# micro_flight.net
KiCad netlist of a schematic drawn in Altium Designer
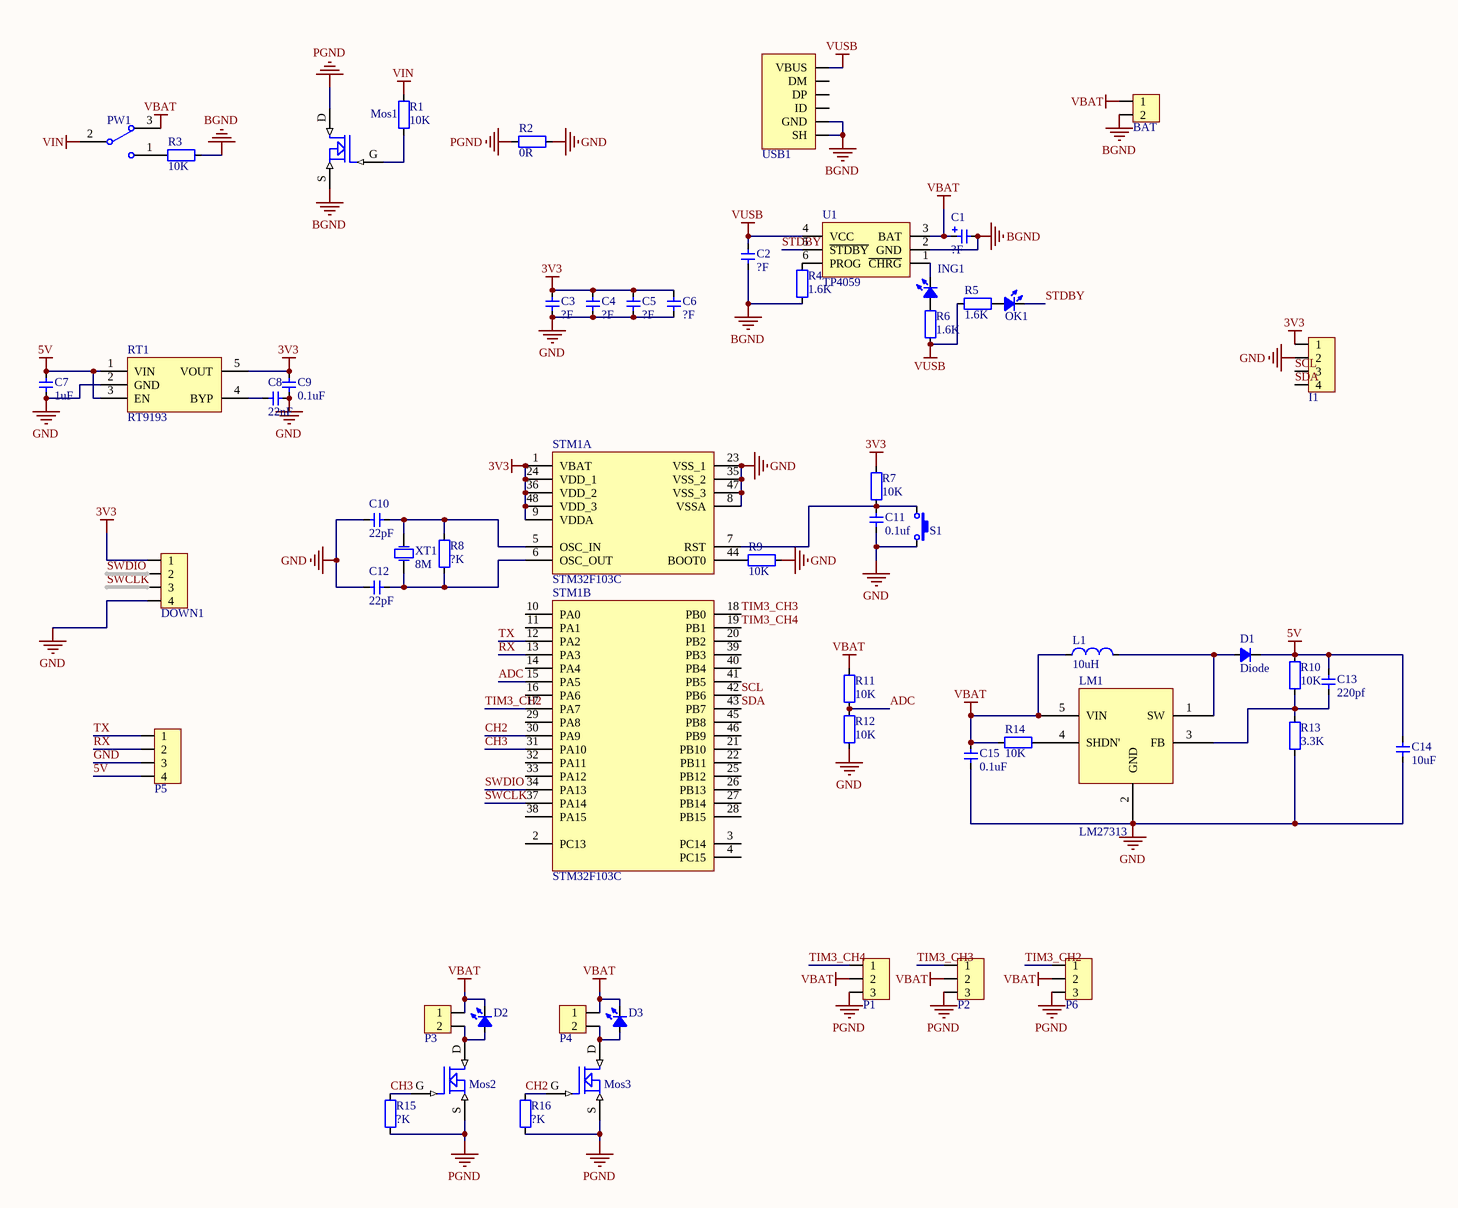
[diagram p0: micro_flight.SchDoc]

(export (version "E")
  (design (tool "Eeschema 10.0.6"))
  (components
    (comp (ref "BAT")
      (value "HDR1x2_2.54")
      (footprint "PCB_ConnectorHDR:HDR1X2_2.54_90")
      (description "Header")
      (libsource (lib "SCH_ConnectorHDR") (part "HDR1x2_2.54"))
    )
    (comp (ref "C1")
      (value "?F")
      (footprint "PCB_PassiveCap:CAP_TAN_D2917")
      (description "Capacitor")
      (fields (field (name "Comment") "Cap_Tan_2917"))
      (libsource (lib "SCH_Passive") (part "Cap_Tan_2917"))
    )
    (comp (ref "C2")
      (value "?F")
      (footprint "PCB_PassiveCap:CAP_0805")
      (description "Capacitor")
      (fields (field (name "Comment") "Cap_0805"))
      (libsource (lib "SCH_Passive") (part "Cap_0805"))
    )
    (comp (ref "C3")
      (value "?F")
      (footprint "PCB_PassiveCap:CAP_0805")
      (description "Capacitor")
      (fields (field (name "Comment") "Cap_0805"))
      (libsource (lib "SCH_Passive") (part "Cap_0805"))
    )
    (comp (ref "C4")
      (value "?F")
      (footprint "PCB_PassiveCap:CAP_0805")
      (description "Capacitor")
      (fields (field (name "Comment") "Cap_0805"))
      (libsource (lib "SCH_Passive") (part "Cap_0805"))
    )
    (comp (ref "C5")
      (value "?F")
      (footprint "PCB_PassiveCap:CAP_0805")
      (description "Capacitor")
      (fields (field (name "Comment") "Cap_0805"))
      (libsource (lib "SCH_Passive") (part "Cap_0805"))
    )
    (comp (ref "C6")
      (value "?F")
      (footprint "PCB_PassiveCap:CAP_0805")
      (description "Capacitor")
      (fields (field (name "Comment") "Cap_0805"))
      (libsource (lib "SCH_Passive") (part "Cap_0805"))
    )
    (comp (ref "C7")
      (value "1uF")
      (footprint "PCB_PassiveCap:CAP_0805")
      (description "Capacitor")
      (fields (field (name "Comment") "Cap_0805"))
      (libsource (lib "SCH_Passive") (part "Cap_0805"))
    )
    (comp (ref "C8")
      (value "22nF")
      (footprint "PCB_PassiveCap:CAP_0805")
      (description "Capacitor")
      (fields (field (name "Comment") "Cap_0805"))
      (libsource (lib "SCH_Passive") (part "Cap_0805"))
    )
    (comp (ref "C9")
      (value "0.1uF")
      (footprint "PCB_PassiveCap:CAP_0805")
      (description "Capacitor")
      (fields (field (name "Comment") "Cap_0805"))
      (libsource (lib "SCH_Passive") (part "Cap_0805"))
    )
    (comp (ref "C10")
      (value "22pF")
      (footprint "PCB_PassiveCap:CAP_0805")
      (description "Capacitor")
      (fields (field (name "Comment") "Cap_0805"))
      (libsource (lib "SCH_Passive") (part "Cap_0805"))
    )
    (comp (ref "C11")
      (value "0.1uf")
      (footprint "PCB_PassiveCap:CAP_0805")
      (description "Capacitor")
      (fields (field (name "Comment") "Cap_0805"))
      (libsource (lib "SCH_Passive") (part "Cap_0805"))
    )
    (comp (ref "C12")
      (value "22pF")
      (footprint "PCB_PassiveCap:CAP_0805")
      (description "Capacitor")
      (fields (field (name "Comment") "Cap_0805"))
      (libsource (lib "SCH_Passive") (part "Cap_0805"))
    )
    (comp (ref "C13")
      (value "220pf")
      (footprint "PCB_PassiveCap:CAP_0805")
      (description "Capacitor")
      (fields (field (name "Comment") "Cap_0805"))
      (libsource (lib "SCH_Passive") (part "Cap_0805"))
    )
    (comp (ref "C14")
      (value "10uF")
      (footprint "PCB_PassiveCap:CAP_0805")
      (description "Capacitor")
      (fields (field (name "Comment") "Cap_0805"))
      (libsource (lib "SCH_Passive") (part "Cap_0805"))
    )
    (comp (ref "C15")
      (value "0.1uF")
      (footprint "PCB_PassiveCap:CAP_0805")
      (description "Capacitor")
      (fields (field (name "Comment") "Cap_0805"))
      (libsource (lib "SCH_Passive") (part "Cap_0805"))
    )
    (comp (ref "D1") (value "Diode") (footprint "LED_0805_RED") (libsource (lib "SCH_Active") (part "Diode")))
    (comp (ref "D2")
      (value "LED_0805")
      (footprint "PCB_ActiveLED:LED_0805_RED")
      (description "LED")
      (libsource (lib "SCH_Active") (part "LED_0805"))
    )
    (comp (ref "D3")
      (value "LED_0805")
      (footprint "PCB_ActiveLED:LED_0805_RED")
      (description "LED")
      (libsource (lib "SCH_Active") (part "LED_0805"))
    )
    (comp (ref "DOWN1")
      (value "HDR1x4_2.54")
      (footprint "PCB_ConnectorHDR:HDR1x4_2.54_180")
      (description "Header")
      (libsource (lib "SCH_ConnectorHDR") (part "HDR1x4_2.54"))
    )
    (comp (ref "I1")
      (value "HDR1x4_2.54")
      (footprint "PCB_ConnectorHDR:HDR1x4_2.54_180")
      (description "Header")
      (libsource (lib "SCH_ConnectorHDR") (part "HDR1x4_2.54"))
    )
    (comp (ref "ING1")
      (value "LED_0805")
      (footprint "PCB_ActiveLED:LED_0805_RED")
      (description "LED")
      (libsource (lib "SCH_Active") (part "LED_0805"))
    )
    (comp (ref "L1")
      (value "10uH")
      (footprint "PCB_PassiveInd:IND_CD32")
      (description "Inductor")
      (fields (field (name "Comment") "Ind_CD32"))
      (libsource (lib "SCH_Passive") (part "Ind_CD32"))
    )
    (comp (ref "LM1")
      (value "LM27313")
      (footprint "SOT23-5")
      (libsource (lib "SCH_IntegratedCircuit") (part "LM27313"))
    )
    (comp (ref "Mos1")
      (value "MOSFET N")
      (footprint "Nmos_SOT23")
      (description "MOS SOT23")
      (libsource (lib "SCH_Active") (part "MOSFET N"))
    )
    (comp (ref "Mos2")
      (value "MOSFET N")
      (footprint "Nmos_SOT23")
      (description "MOS SOT23")
      (libsource (lib "SCH_Active") (part "MOSFET N"))
    )
    (comp (ref "Mos3")
      (value "MOSFET N")
      (footprint "Nmos_SOT23")
      (description "MOS SOT23")
      (libsource (lib "SCH_Active") (part "MOSFET N"))
    )
    (comp (ref "OK1")
      (value "LED_0805")
      (footprint "PCB_ActiveLED:LED_0805_GREEN")
      (description "LED")
      (libsource (lib "SCH_Active") (part "LED_0805"))
    )
    (comp (ref "P1")
      (value "HDR1x3_2.54")
      (footprint "PCB_ConnectorHDR:HDR1X3_2.54_180")
      (description "Header")
      (libsource (lib "SCH_ConnectorHDR") (part "HDR1x3_2.54"))
    )
    (comp (ref "P2")
      (value "HDR1x3_2.54")
      (footprint "PCB_ConnectorHDR:HDR1X3_2.54_180")
      (description "Header")
      (libsource (lib "SCH_ConnectorHDR") (part "HDR1x3_2.54"))
    )
    (comp (ref "P3")
      (value "HDR1x2_2.54")
      (footprint "PCB_ConnectorHDR:HDR1X2_2.54_180")
      (description "Header")
      (libsource (lib "SCH_ConnectorHDR") (part "HDR1x2_2.54T"))
    )
    (comp (ref "P4")
      (value "HDR1x2_2.54")
      (footprint "PCB_ConnectorHDR:HDR1X2_2.54_180")
      (description "Header")
      (libsource (lib "SCH_ConnectorHDR") (part "HDR1x2_2.54T"))
    )
    (comp (ref "P5")
      (value "HDR1x4_2.54")
      (footprint "PCB_ConnectorHDR:HDR1x4_2.54_180")
      (description "Header")
      (libsource (lib "SCH_ConnectorHDR") (part "HDR1x4_2.54"))
    )
    (comp (ref "P6")
      (value "HDR1x3_2.54")
      (footprint "PCB_ConnectorHDR:HDR1X3_2.54_180")
      (description "Header")
      (libsource (lib "SCH_ConnectorHDR") (part "HDR1x3_2.54"))
    )
    (comp (ref "PW1")
      (value "SwitchSPDT_2.8x6.6_90")
      (footprint "PCB_Switch:SwitchSPDT_2.8X6.6_90")
      (description "Switch")
      (libsource (lib "SCH_Switch") (part "SwitchSPDT_2.8x6.6_90"))
    )
    (comp (ref "R1")
      (value "10K")
      (footprint "PCB_PassiveRes:RES_0805")
      (description "Resistor")
      (fields (field (name "Comment") "Res_0805"))
      (libsource (lib "SCH_Passive") (part "Res_0805"))
    )
    (comp (ref "R2")
      (value "0R")
      (footprint "PCB_PassiveRes:RES_0805")
      (description "Resistor")
      (fields (field (name "Comment") "Res_0805"))
      (libsource (lib "") (part "Res_0805_2"))
    )
    (comp (ref "R3")
      (value "10K")
      (footprint "PCB_PassiveRes:RES_0805")
      (description "Resistor")
      (fields (field (name "Comment") "Res_0805"))
      (libsource (lib "") (part "Res_0805_2"))
    )
    (comp (ref "R4")
      (value "1.6K")
      (footprint "PCB_PassiveRes:RES_0805")
      (description "Resistor")
      (fields (field (name "Comment") "Res_0805"))
      (libsource (lib "SCH_Passive") (part "Res_0805"))
    )
    (comp (ref "R5")
      (value "1.6K")
      (footprint "PCB_PassiveRes:RES_0805")
      (description "Resistor")
      (fields (field (name "Comment") "Res_0805"))
      (libsource (lib "") (part "Res_0805_2"))
    )
    (comp (ref "R6")
      (value "1.6K")
      (footprint "PCB_PassiveRes:RES_0805")
      (description "Resistor")
      (fields (field (name "Comment") "Res_0805"))
      (libsource (lib "SCH_Passive") (part "Res_0805"))
    )
    (comp (ref "R7")
      (value "10K")
      (footprint "PCB_PassiveRes:RES_0805")
      (description "Resistor")
      (fields (field (name "Comment") "Res_0805"))
      (libsource (lib "SCH_Passive") (part "Res_0805"))
    )
    (comp (ref "R8")
      (value "?K")
      (footprint "PCB_PassiveRes:RES_0805")
      (description "Resistor")
      (fields (field (name "Comment") "Res_0805"))
      (libsource (lib "SCH_Passive") (part "Res_0805"))
    )
    (comp (ref "R9")
      (value "10K")
      (footprint "PCB_PassiveRes:RES_0805")
      (description "Resistor")
      (fields (field (name "Comment") "Res_0805"))
      (libsource (lib "") (part "Res_0805_1"))
    )
    (comp (ref "R10")
      (value "10K")
      (footprint "PCB_PassiveRes:RES_0805")
      (description "Resistor")
      (fields (field (name "Comment") "Res_0805"))
      (libsource (lib "SCH_Passive") (part "Res_0805"))
    )
    (comp (ref "R11")
      (value "10K")
      (footprint "PCB_PassiveRes:RES_0805")
      (description "Resistor")
      (fields (field (name "Comment") "Res_0805"))
      (libsource (lib "") (part "Res_0805_3"))
    )
    (comp (ref "R12")
      (value "10K")
      (footprint "PCB_PassiveRes:RES_0805")
      (description "Resistor")
      (fields (field (name "Comment") "Res_0805"))
      (libsource (lib "SCH_Passive") (part "Res_0805"))
    )
    (comp (ref "R13")
      (value "3.3K")
      (footprint "PCB_PassiveRes:RES_0805")
      (description "Resistor")
      (fields (field (name "Comment") "Res_0805"))
      (libsource (lib "SCH_Passive") (part "Res_0805"))
    )
    (comp (ref "R14")
      (value "10K")
      (footprint "PCB_PassiveRes:RES_0805")
      (description "Resistor")
      (fields (field (name "Comment") "Res_0805"))
      (libsource (lib "") (part "Res_0805_2"))
    )
    (comp (ref "R15")
      (value "?K")
      (footprint "PCB_PassiveRes:RES_0805")
      (description "Resistor")
      (fields (field (name "Comment") "Res_0805"))
      (libsource (lib "") (part "Res_0805_3"))
    )
    (comp (ref "R16")
      (value "?K")
      (footprint "PCB_PassiveRes:RES_0805")
      (description "Resistor")
      (fields (field (name "Comment") "Res_0805"))
      (libsource (lib "") (part "Res_0805_3"))
    )
    (comp (ref "RT1")
      (value "RT9193")
      (footprint "PCB_IntegratedCircuit:SOT23-5")
      (description "Power")
      (libsource (lib "SCH_IntegratedCircuit") (part "RT9193"))
    )
    (comp (ref "S1")
      (value "ButtonTACT_3x6x2.5_180")
      (footprint "PCB_Switch:ButtonTACT_3x6x2.5_180")
      (description "Button")
      (libsource (lib "SCH_Switch") (part "ButtonTACT_3x6x2.5_180"))
    )
    (comp (ref "STM1")
      (value "STM32F103C")
      (footprint "PCB_IntegratedCircuit:LQFP_P0.5_48")
      (description "MCU")
      (libsource (lib "SCH_IntegratedCircuit") (part "STM32F103C"))
    )
    (comp (ref "U1")
      (value "TP4059")
      (footprint "SOT23-6")
      (libsource (lib "SCH_IntegratedCircuit") (part "TP4059"))
    )
    (comp (ref "USB1")
      (value "USB_Micro")
      (footprint "PCB_USB:USB_Micro-AB")
      (description "USB")
      (libsource (lib "SCH_USB") (part "USB_Micro"))
    )
    (comp (ref "XT1")
      (value "8M")
      (footprint "PCB_Oscillator:XT_5032_2")
      (description "Crystal Oscillator")
      (fields (field (name "Comment") "XTAL_5032_2P"))
      (libsource (lib "SCH_Oscillator") (part "XTAL_5032_2P"))
    )
  )
  (nets
    (net (code "1") (name "/ADC") (class "Default")
      (node (ref "R11") (pin "2") (pinfunction "2_2") (pintype "passive"))
      (node (ref "R12") (pin "2") (pinfunction "2_2") (pintype "passive"))
      (node (ref "STM1") (pin "15") (pinfunction "PA5_15") (pintype "passive"))
    )
    (net (code "2") (name "/CH2") (class "Default")
      (node (ref "Mos3") (pin "G") (pinfunction "G_G") (pintype "input"))
      (node (ref "R16") (pin "1") (pinfunction "1_1") (pintype "passive"))
      (node (ref "STM1") (pin "30") (pinfunction "PA9_30") (pintype "passive"))
    )
    (net (code "3") (name "/CH3") (class "Default")
      (node (ref "Mos2") (pin "G") (pinfunction "G_G") (pintype "input"))
      (node (ref "R15") (pin "1") (pinfunction "1_1") (pintype "passive"))
      (node (ref "STM1") (pin "31") (pinfunction "PA10_31") (pintype "passive"))
    )
    (net (code "4") (name "/RX") (class "Default")
      (node (ref "P5") (pin "2") (pinfunction "2_2") (pintype "passive"))
      (node (ref "STM1") (pin "13") (pinfunction "PA3_13") (pintype "passive"))
    )
    (net (code "5") (name "/SCL") (class "Default")
      (node (ref "I1") (pin "3") (pinfunction "3_3") (pintype "passive"))
      (node (ref "STM1") (pin "42") (pinfunction "PB6_42") (pintype "passive"))
    )
    (net (code "6") (name "/SDA") (class "Default")
      (node (ref "I1") (pin "4") (pinfunction "4_4") (pintype "passive"))
      (node (ref "STM1") (pin "43") (pinfunction "PB7_43") (pintype "passive"))
    )
    (net (code "7") (name "/STDBY") (class "Default")
      (node (ref "OK1") (pin "2") (pinfunction "K_2") (pintype "passive"))
      (node (ref "U1") (pin "5") (pinfunction "~{STDBY}_5") (pintype "passive"))
    )
    (net (code "8") (name "/SWCLK") (class "Default")
      (node (ref "DOWN1") (pin "3") (pinfunction "3_3") (pintype "passive"))
      (node (ref "STM1") (pin "37") (pinfunction "PA14_37") (pintype "passive"))
    )
    (net (code "9") (name "/SWDIO") (class "Default")
      (node (ref "DOWN1") (pin "2") (pinfunction "2_2") (pintype "passive"))
      (node (ref "STM1") (pin "34") (pinfunction "PA13_34") (pintype "passive"))
    )
    (net (code "10") (name "/TIM3_CH2") (class "Default")
      (node (ref "P6") (pin "1") (pinfunction "1_1") (pintype "passive"))
      (node (ref "STM1") (pin "17") (pinfunction "PA7_17") (pintype "passive"))
    )
    (net (code "11") (name "/TIM3_CH3") (class "Default")
      (node (ref "P2") (pin "1") (pinfunction "1_1") (pintype "passive"))
      (node (ref "STM1") (pin "18") (pinfunction "PB0_18") (pintype "passive"))
    )
    (net (code "12") (name "/TIM3_CH4") (class "Default")
      (node (ref "P1") (pin "1") (pinfunction "1_1") (pintype "passive"))
      (node (ref "STM1") (pin "19") (pinfunction "PB1_19") (pintype "passive"))
    )
    (net (code "13") (name "/TX") (class "Default")
      (node (ref "P5") (pin "1") (pinfunction "1_1") (pintype "passive"))
      (node (ref "STM1") (pin "12") (pinfunction "PA2_12") (pintype "passive"))
    )
    (net (code "14") (name "3V3") (class "Default")
      (node (ref "C3") (pin "2") (pinfunction "2_2") (pintype "passive"))
      (node (ref "C4") (pin "2") (pinfunction "2_2") (pintype "passive"))
      (node (ref "C5") (pin "2") (pinfunction "2_2") (pintype "passive"))
      (node (ref "C6") (pin "2") (pinfunction "2_2") (pintype "passive"))
      (node (ref "C9") (pin "2") (pinfunction "2_2") (pintype "passive"))
      (node (ref "DOWN1") (pin "1") (pinfunction "1_1") (pintype "passive"))
      (node (ref "I1") (pin "1") (pinfunction "1_1") (pintype "passive"))
      (node (ref "R7") (pin "2") (pinfunction "2_2") (pintype "passive"))
      (node (ref "RT1") (pin "5") (pinfunction "VOUT_5") (pintype "passive"))
      (node (ref "STM1") (pin "1") (pinfunction "VBAT_1") (pintype "passive"))
      (node (ref "STM1") (pin "24") (pinfunction "VDD_1_24") (pintype "passive"))
      (node (ref "STM1") (pin "36") (pinfunction "VDD_2_36") (pintype "passive"))
      (node (ref "STM1") (pin "48") (pinfunction "VDD_3_48") (pintype "passive"))
      (node (ref "STM1") (pin "9") (pinfunction "VDDA_9") (pintype "passive"))
    )
    (net (code "15") (name "5V") (class "Default")
      (node (ref "C13") (pin "2") (pinfunction "2_2") (pintype "passive"))
      (node (ref "C14") (pin "2") (pinfunction "2_2") (pintype "passive"))
      (node (ref "C7") (pin "2") (pinfunction "2_2") (pintype "passive"))
      (node (ref "D1") (pin "2") (pinfunction "K_2") (pintype "passive"))
      (node (ref "P5") (pin "4") (pinfunction "4_4") (pintype "passive"))
      (node (ref "R10") (pin "2") (pinfunction "2_2") (pintype "passive"))
      (node (ref "RT1") (pin "1") (pinfunction "VIN_1") (pintype "passive"))
      (node (ref "RT1") (pin "3") (pinfunction "EN_3") (pintype "power_in"))
    )
    (net (code "16") (name "BGND") (class "Default")
      (node (ref "BAT") (pin "2") (pinfunction "2_2") (pintype "passive"))
      (node (ref "C1") (pin "2") (pinfunction "2_2") (pintype "passive"))
      (node (ref "C2") (pin "1") (pinfunction "1_1") (pintype "passive"))
      (node (ref "Mos1") (pin "S") (pinfunction "S_S") (pintype "input"))
      (node (ref "R3") (pin "1") (pinfunction "1_1") (pintype "passive"))
      (node (ref "R4") (pin "1") (pinfunction "1_1") (pintype "passive"))
      (node (ref "U1") (pin "2") (pinfunction "GND_2") (pintype "passive"))
      (node (ref "USB1") (pin "0") (pinfunction "SH_0") (pintype "passive"))
      (node (ref "USB1") (pin "5") (pinfunction "GND_5") (pintype "passive"))
    )
    (net (code "17") (name "GND") (class "Default")
      (node (ref "C10") (pin "1") (pinfunction "1_1") (pintype "passive"))
      (node (ref "C11") (pin "1") (pinfunction "1_1") (pintype "passive"))
      (node (ref "C12") (pin "1") (pinfunction "1_1") (pintype "passive"))
      (node (ref "C14") (pin "1") (pinfunction "1_1") (pintype "passive"))
      (node (ref "C15") (pin "1") (pinfunction "1_1") (pintype "passive"))
      (node (ref "C3") (pin "1") (pinfunction "1_1") (pintype "passive"))
      (node (ref "C4") (pin "1") (pinfunction "1_1") (pintype "passive"))
      (node (ref "C5") (pin "1") (pinfunction "1_1") (pintype "passive"))
      (node (ref "C6") (pin "1") (pinfunction "1_1") (pintype "passive"))
      (node (ref "C7") (pin "1") (pinfunction "1_1") (pintype "passive"))
      (node (ref "C8") (pin "2") (pinfunction "2_2") (pintype "passive"))
      (node (ref "C9") (pin "1") (pinfunction "1_1") (pintype "passive"))
      (node (ref "DOWN1") (pin "4") (pinfunction "4_4") (pintype "passive"))
      (node (ref "I1") (pin "2") (pinfunction "2_2") (pintype "passive"))
      (node (ref "LM1") (pin "2") (pinfunction "GND_2") (pintype "passive"))
      (node (ref "P5") (pin "3") (pinfunction "3_3") (pintype "passive"))
      (node (ref "R12") (pin "1") (pinfunction "1_1") (pintype "passive"))
      (node (ref "R13") (pin "1") (pinfunction "1_1") (pintype "passive"))
      (node (ref "R2") (pin "1") (pinfunction "1_1") (pintype "passive"))
      (node (ref "R9") (pin "2") (pinfunction "2_2") (pintype "passive"))
      (node (ref "RT1") (pin "2") (pinfunction "GND_2") (pintype "passive"))
      (node (ref "S1") (pin "2") (pinfunction "2_2") (pintype "passive"))
      (node (ref "STM1") (pin "23") (pinfunction "VSS_1_23") (pintype "passive"))
      (node (ref "STM1") (pin "35") (pinfunction "VSS_2_35") (pintype "passive"))
      (node (ref "STM1") (pin "47") (pinfunction "VSS_3_47") (pintype "passive"))
      (node (ref "STM1") (pin "8") (pinfunction "VSSA_8") (pintype "passive"))
    )
    (net (code "18") (name "Net-(D1-A)") (class "Default")
      (node (ref "D1") (pin "1") (pinfunction "A_1") (pintype "passive"))
      (node (ref "L1") (pin "2") (pinfunction "2_2") (pintype "passive"))
      (node (ref "LM1") (pin "1") (pinfunction "SW_1") (pintype "passive"))
    )
    (net (code "19") (name "Net-(D2-A)") (class "Default")
      (node (ref "D2") (pin "1") (pinfunction "A_1") (pintype "passive"))
      (node (ref "Mos2") (pin "D") (pinfunction "D_D") (pintype "input"))
      (node (ref "P3") (pin "2") (pinfunction "2_2") (pintype "passive"))
    )
    (net (code "20") (name "Net-(D3-A)") (class "Default")
      (node (ref "D3") (pin "1") (pinfunction "A_1") (pintype "passive"))
      (node (ref "Mos3") (pin "D") (pinfunction "D_D") (pintype "input"))
      (node (ref "P4") (pin "2") (pinfunction "2_2") (pintype "passive"))
    )
    (net (code "21") (name "Net-(ING1-A)") (class "Default")
      (node (ref "ING1") (pin "1") (pinfunction "A_1") (pintype "passive"))
      (node (ref "R6") (pin "2") (pinfunction "2_2") (pintype "passive"))
    )
    (net (code "22") (name "Net-(ING1-K)") (class "Default")
      (node (ref "ING1") (pin "2") (pinfunction "K_2") (pintype "passive"))
      (node (ref "U1") (pin "1") (pinfunction "~{CHRG}_1") (pintype "passive"))
    )
    (net (code "23") (name "Net-(LM1-FB)") (class "Default")
      (node (ref "C13") (pin "1") (pinfunction "1_1") (pintype "passive"))
      (node (ref "LM1") (pin "3") (pinfunction "FB_3") (pintype "passive"))
      (node (ref "R10") (pin "1") (pinfunction "1_1") (pintype "passive"))
      (node (ref "R13") (pin "2") (pinfunction "2_2") (pintype "passive"))
    )
    (net (code "24") (name "Net-(LM1-SHDN')") (class "Default")
      (node (ref "LM1") (pin "4") (pinfunction "SHDN'_4") (pintype "passive"))
      (node (ref "R14") (pin "1") (pinfunction "1_1") (pintype "passive"))
    )
    (net (code "25") (name "Net-(Mos1-PadG)") (class "Default")
      (node (ref "Mos1") (pin "G") (pinfunction "G_G") (pintype "input"))
      (node (ref "R1") (pin "1") (pinfunction "1_1") (pintype "passive"))
    )
    (net (code "26") (name "Net-(OK1-A)") (class "Default")
      (node (ref "OK1") (pin "1") (pinfunction "A_1") (pintype "passive"))
      (node (ref "R5") (pin "1") (pinfunction "1_1") (pintype "passive"))
    )
    (net (code "27") (name "Net-(PW1-Pad1)") (class "Default")
      (node (ref "PW1") (pin "1") (pinfunction "1_1") (pintype "passive"))
      (node (ref "R3") (pin "2") (pinfunction "2_2") (pintype "passive"))
    )
    (net (code "28") (name "Net-(RT1-BYP)") (class "Default")
      (node (ref "C8") (pin "1") (pinfunction "1_1") (pintype "passive"))
      (node (ref "RT1") (pin "4") (pinfunction "BYP_4") (pintype "passive"))
    )
    (net (code "29") (name "Net-(STM1A-BOOT0)") (class "Default")
      (node (ref "R9") (pin "1") (pinfunction "1_1") (pintype "passive"))
      (node (ref "STM1") (pin "44") (pinfunction "BOOT0_44") (pintype "passive"))
    )
    (net (code "30") (name "Net-(STM1A-OSC_IN)") (class "Default")
      (node (ref "C10") (pin "2") (pinfunction "2_2") (pintype "passive"))
      (node (ref "R8") (pin "2") (pinfunction "2_2") (pintype "passive"))
      (node (ref "STM1") (pin "5") (pinfunction "OSC_IN_5") (pintype "passive"))
      (node (ref "XT1") (pin "2") (pinfunction "OSC2_2") (pintype "passive"))
    )
    (net (code "31") (name "Net-(STM1A-OSC_OUT)") (class "Default")
      (node (ref "C12") (pin "2") (pinfunction "2_2") (pintype "passive"))
      (node (ref "R8") (pin "1") (pinfunction "1_1") (pintype "passive"))
      (node (ref "STM1") (pin "6") (pinfunction "OSC_OUT_6") (pintype "passive"))
      (node (ref "XT1") (pin "1") (pinfunction "OSC1_1") (pintype "passive"))
    )
    (net (code "32") (name "Net-(STM1A-RST)") (class "Default")
      (node (ref "C11") (pin "2") (pinfunction "2_2") (pintype "passive"))
      (node (ref "R7") (pin "1") (pinfunction "1_1") (pintype "passive"))
      (node (ref "S1") (pin "1") (pinfunction "1_1") (pintype "passive"))
      (node (ref "STM1") (pin "7") (pinfunction "RST_7") (pintype "passive"))
    )
    (net (code "33") (name "Net-(U1-PROG)") (class "Default")
      (node (ref "R4") (pin "2") (pinfunction "2_2") (pintype "passive"))
      (node (ref "U1") (pin "6") (pinfunction "PROG_6") (pintype "passive"))
    )
    (net (code "34") (name "PGND") (class "Default")
      (node (ref "Mos1") (pin "D") (pinfunction "D_D") (pintype "input"))
      (node (ref "Mos2") (pin "S") (pinfunction "S_S") (pintype "input"))
      (node (ref "Mos3") (pin "S") (pinfunction "S_S") (pintype "input"))
      (node (ref "P1") (pin "3") (pinfunction "3_3") (pintype "passive"))
      (node (ref "P2") (pin "3") (pinfunction "3_3") (pintype "passive"))
      (node (ref "P6") (pin "3") (pinfunction "3_3") (pintype "passive"))
      (node (ref "R15") (pin "2") (pinfunction "2_2") (pintype "passive"))
      (node (ref "R16") (pin "2") (pinfunction "2_2") (pintype "passive"))
      (node (ref "R2") (pin "2") (pinfunction "2_2") (pintype "passive"))
    )
    (net (code "35") (name "VBAT") (class "Default")
      (node (ref "BAT") (pin "1") (pinfunction "1_1") (pintype "passive"))
      (node (ref "C1") (pin "1") (pinfunction "1_1") (pintype "passive"))
      (node (ref "C15") (pin "2") (pinfunction "2_2") (pintype "passive"))
      (node (ref "D2") (pin "2") (pinfunction "K_2") (pintype "passive"))
      (node (ref "D3") (pin "2") (pinfunction "K_2") (pintype "passive"))
      (node (ref "L1") (pin "1") (pinfunction "1_1") (pintype "passive"))
      (node (ref "LM1") (pin "5") (pinfunction "VIN_5") (pintype "passive"))
      (node (ref "P1") (pin "2") (pinfunction "2_2") (pintype "passive"))
      (node (ref "P2") (pin "2") (pinfunction "2_2") (pintype "passive"))
      (node (ref "P3") (pin "1") (pinfunction "1_1") (pintype "passive"))
      (node (ref "P4") (pin "1") (pinfunction "1_1") (pintype "passive"))
      (node (ref "P6") (pin "2") (pinfunction "2_2") (pintype "passive"))
      (node (ref "PW1") (pin "3") (pinfunction "3_3") (pintype "passive"))
      (node (ref "R11") (pin "1") (pinfunction "1_1") (pintype "passive"))
      (node (ref "R14") (pin "2") (pinfunction "2_2") (pintype "passive"))
      (node (ref "U1") (pin "3") (pinfunction "BAT_3") (pintype "passive"))
    )
    (net (code "36") (name "VIN") (class "Default")
      (node (ref "PW1") (pin "2") (pinfunction "2_2") (pintype "passive"))
      (node (ref "R1") (pin "2") (pinfunction "2_2") (pintype "passive"))
    )
    (net (code "37") (name "VUSB") (class "Default")
      (node (ref "C2") (pin "2") (pinfunction "2_2") (pintype "passive"))
      (node (ref "R5") (pin "2") (pinfunction "2_2") (pintype "passive"))
      (node (ref "R6") (pin "1") (pinfunction "1_1") (pintype "passive"))
      (node (ref "U1") (pin "4") (pinfunction "VCC_4") (pintype "passive"))
      (node (ref "USB1") (pin "1") (pinfunction "VBUS_1") (pintype "passive"))
    )
    (net (code "38") (name "unconnected-(STM1B-PA0-Pad10)") (class "Default")
      (node (ref "STM1") (pin "10") (pinfunction "PA0_10") (pintype "passive"))
    )
    (net (code "39") (name "unconnected-(STM1B-PA1-Pad11)") (class "Default")
      (node (ref "STM1") (pin "11") (pinfunction "PA1_11") (pintype "passive"))
    )
    (net (code "40") (name "unconnected-(STM1B-PA4-Pad14)") (class "Default")
      (node (ref "STM1") (pin "14") (pinfunction "PA4_14") (pintype "passive"))
    )
    (net (code "41") (name "unconnected-(STM1B-PA6-Pad16)") (class "Default")
      (node (ref "STM1") (pin "16") (pinfunction "PA6_16") (pintype "passive"))
    )
    (net (code "42") (name "unconnected-(STM1B-PA8-Pad29)") (class "Default")
      (node (ref "STM1") (pin "29") (pinfunction "PA8_29") (pintype "passive"))
    )
    (net (code "43") (name "unconnected-(STM1B-PA11-Pad32)") (class "Default")
      (node (ref "STM1") (pin "32") (pinfunction "PA11_32") (pintype "passive"))
    )
    (net (code "44") (name "unconnected-(STM1B-PA12-Pad33)") (class "Default")
      (node (ref "STM1") (pin "33") (pinfunction "PA12_33") (pintype "passive"))
    )
    (net (code "45") (name "unconnected-(STM1B-PA15-Pad38)") (class "Default")
      (node (ref "STM1") (pin "38") (pinfunction "PA15_38") (pintype "passive"))
    )
    (net (code "46") (name "unconnected-(STM1B-PB2-Pad20)") (class "Default")
      (node (ref "STM1") (pin "20") (pinfunction "PB2_20") (pintype "passive"))
    )
    (net (code "47") (name "unconnected-(STM1B-PB3-Pad39)") (class "Default")
      (node (ref "STM1") (pin "39") (pinfunction "PB3_39") (pintype "passive"))
    )
    (net (code "48") (name "unconnected-(STM1B-PB4-Pad40)") (class "Default")
      (node (ref "STM1") (pin "40") (pinfunction "PB4_40") (pintype "passive"))
    )
    (net (code "49") (name "unconnected-(STM1B-PB5-Pad41)") (class "Default")
      (node (ref "STM1") (pin "41") (pinfunction "PB5_41") (pintype "passive"))
    )
    (net (code "50") (name "unconnected-(STM1B-PB8-Pad45)") (class "Default")
      (node (ref "STM1") (pin "45") (pinfunction "PB8_45") (pintype "passive"))
    )
    (net (code "51") (name "unconnected-(STM1B-PB9-Pad46)") (class "Default")
      (node (ref "STM1") (pin "46") (pinfunction "PB9_46") (pintype "passive"))
    )
    (net (code "52") (name "unconnected-(STM1B-PB10-Pad21)") (class "Default")
      (node (ref "STM1") (pin "21") (pinfunction "PB10_21") (pintype "passive"))
    )
    (net (code "53") (name "unconnected-(STM1B-PB11-Pad22)") (class "Default")
      (node (ref "STM1") (pin "22") (pinfunction "PB11_22") (pintype "passive"))
    )
    (net (code "54") (name "unconnected-(STM1B-PB12-Pad25)") (class "Default")
      (node (ref "STM1") (pin "25") (pinfunction "PB12_25") (pintype "passive"))
    )
    (net (code "55") (name "unconnected-(STM1B-PB13-Pad26)") (class "Default")
      (node (ref "STM1") (pin "26") (pinfunction "PB13_26") (pintype "passive"))
    )
    (net (code "56") (name "unconnected-(STM1B-PB14-Pad27)") (class "Default")
      (node (ref "STM1") (pin "27") (pinfunction "PB14_27") (pintype "passive"))
    )
    (net (code "57") (name "unconnected-(STM1B-PB15-Pad28)") (class "Default")
      (node (ref "STM1") (pin "28") (pinfunction "PB15_28") (pintype "passive"))
    )
    (net (code "58") (name "unconnected-(STM1B-PC13-Pad2)") (class "Default")
      (node (ref "STM1") (pin "2") (pinfunction "PC13_2") (pintype "passive"))
    )
    (net (code "59") (name "unconnected-(STM1B-PC14-Pad3)") (class "Default")
      (node (ref "STM1") (pin "3") (pinfunction "PC14_3") (pintype "passive"))
    )
    (net (code "60") (name "unconnected-(STM1B-PC15-Pad4)") (class "Default")
      (node (ref "STM1") (pin "4") (pinfunction "PC15_4") (pintype "passive"))
    )
    (net (code "61") (name "unconnected-(USB1-DM-Pad2)") (class "Default")
      (node (ref "USB1") (pin "2") (pinfunction "DM_2") (pintype "passive"))
    )
    (net (code "62") (name "unconnected-(USB1-DP-Pad3)") (class "Default")
      (node (ref "USB1") (pin "3") (pinfunction "DP_3") (pintype "passive"))
    )
    (net (code "63") (name "unconnected-(USB1-ID-Pad4)") (class "Default")
      (node (ref "USB1") (pin "4") (pinfunction "ID_4") (pintype "passive"))
    )
  )
)
